# REDOUBLER.net
KiCad netlist of a schematic drawn in EAGLE
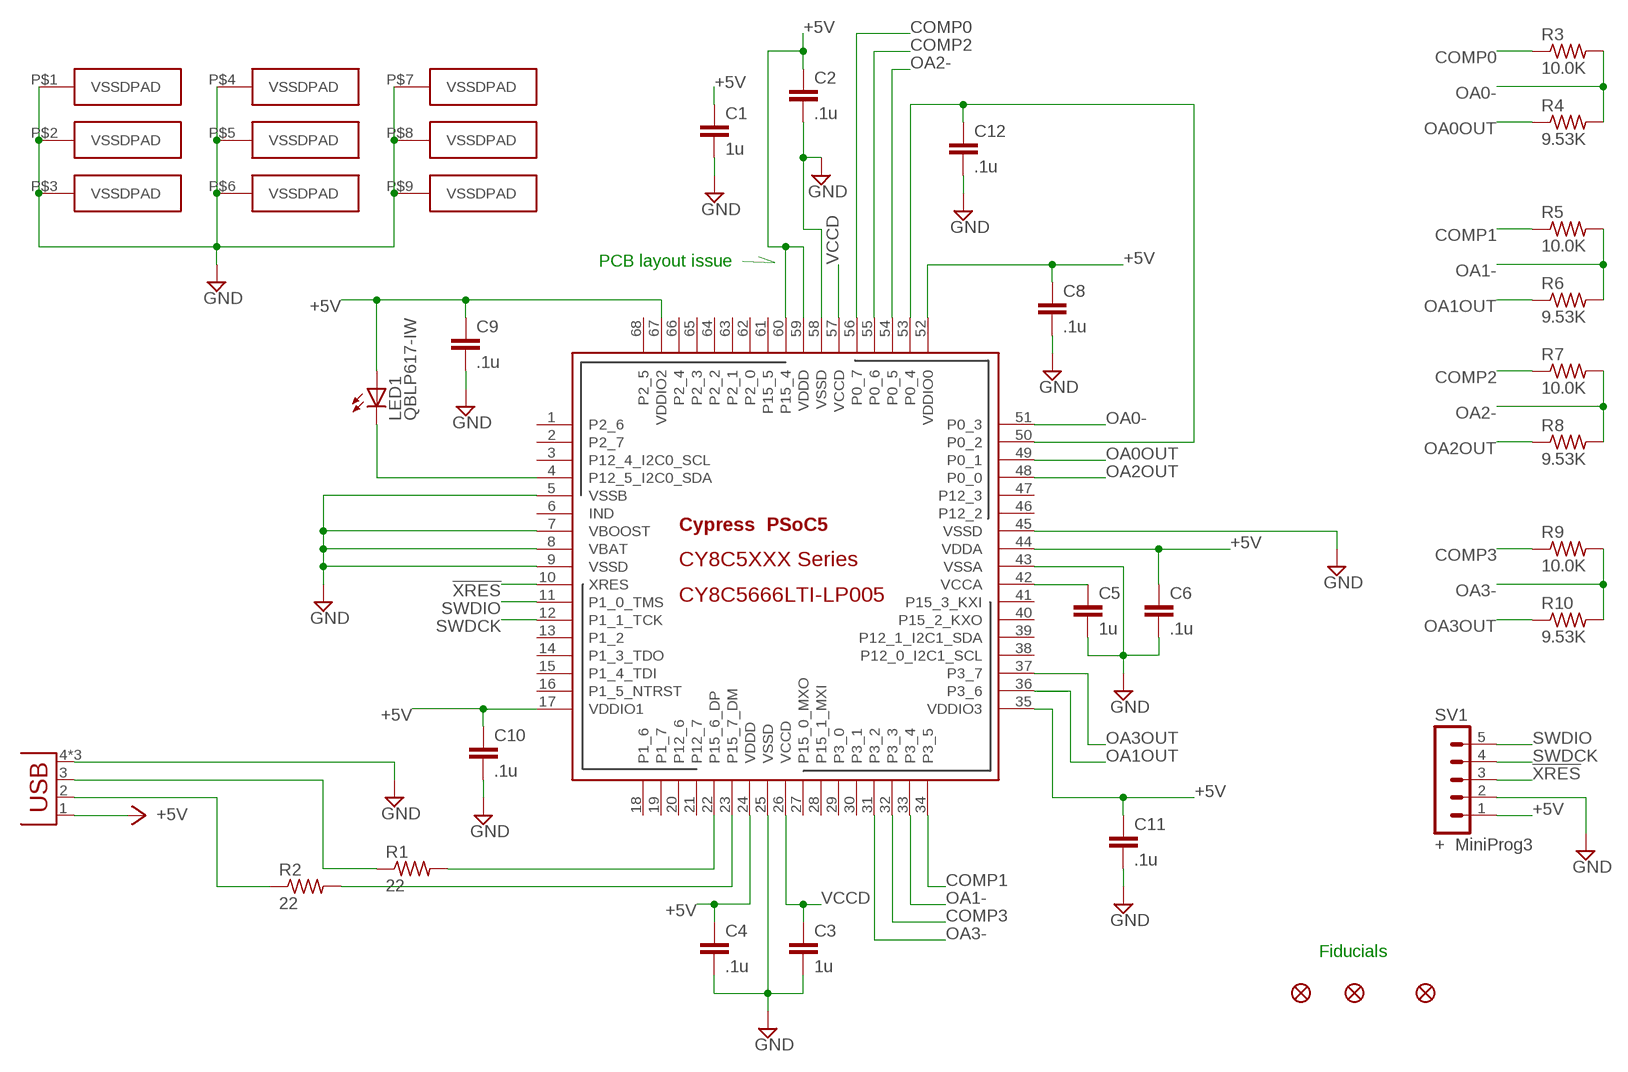
[diagram p0: schematic, sheet 1]

(export (version "E")
  (design (tool "Eeschema 10.0.6"))
  (components
    (comp (ref "C1")
      (value "1u")
      (footprint "eagle-import:C0402")
      (libsource (lib "eagle-import") (part "C-EUC0402"))
    )
    (comp (ref "C2")
      (value ".1u")
      (footprint "eagle-import:C0402")
      (libsource (lib "eagle-import") (part "C-EUC0402"))
    )
    (comp (ref "C3")
      (value "1u")
      (footprint "eagle-import:C0402")
      (libsource (lib "eagle-import") (part "C-EUC0402"))
    )
    (comp (ref "C4")
      (value ".1u")
      (footprint "eagle-import:C0402")
      (libsource (lib "eagle-import") (part "C-EUC0402"))
    )
    (comp (ref "C5")
      (value "1u")
      (footprint "eagle-import:C0402")
      (libsource (lib "eagle-import") (part "C-EUC0402"))
    )
    (comp (ref "C6")
      (value ".1u")
      (footprint "eagle-import:C0402")
      (libsource (lib "eagle-import") (part "C-EUC0402"))
    )
    (comp (ref "C8")
      (value ".1u")
      (footprint "eagle-import:C0402")
      (libsource (lib "eagle-import") (part "C-EUC0402"))
    )
    (comp (ref "C9")
      (value ".1u")
      (footprint "eagle-import:C0402")
      (libsource (lib "eagle-import") (part "C-EUC0402"))
    )
    (comp (ref "C10")
      (value ".1u")
      (footprint "eagle-import:C0402")
      (libsource (lib "eagle-import") (part "C-EUC0402"))
    )
    (comp (ref "C11")
      (value ".1u")
      (footprint "eagle-import:C0402")
      (libsource (lib "eagle-import") (part "C-EUC0402"))
    )
    (comp (ref "C12")
      (value ".1u")
      (footprint "eagle-import:C0402")
      (libsource (lib "eagle-import") (part "C-EUC0402"))
    )
    (comp (ref "FID1")
      (value "FIDUCIALUFIDUCIAL")
      (footprint "eagle-import:MICRO-FIDUCIAL")
      (libsource (lib "eagle-import") (part "FIDUCIALUFIDUCIAL"))
    )
    (comp (ref "FID2")
      (value "FIDUCIALUFIDUCIAL")
      (footprint "eagle-import:MICRO-FIDUCIAL")
      (libsource (lib "eagle-import") (part "FIDUCIALUFIDUCIAL"))
    )
    (comp (ref "FID3")
      (value "FIDUCIALUFIDUCIAL")
      (footprint "eagle-import:MICRO-FIDUCIAL")
      (libsource (lib "eagle-import") (part "FIDUCIALUFIDUCIAL"))
    )
    (comp (ref "LED1")
      (value "QBLP617-IW")
      (footprint "eagle-import:CHIP-LED0603")
      (libsource (lib "eagle-import") (part "LEDCHIP-LED0603"))
    )
    (comp (ref "R1")
      (value "22")
      (footprint "eagle-import:R0402")
      (libsource (lib "eagle-import") (part "R-US_R0402"))
    )
    (comp (ref "R2")
      (value "22")
      (footprint "eagle-import:R0402")
      (libsource (lib "eagle-import") (part "R-US_R0402"))
    )
    (comp (ref "R3")
      (value "10.0K")
      (footprint "eagle-import:R0402")
      (libsource (lib "eagle-import") (part "R-US_R0402"))
    )
    (comp (ref "R4")
      (value "9.53K")
      (footprint "eagle-import:R0402")
      (libsource (lib "eagle-import") (part "R-US_R0402"))
    )
    (comp (ref "R5")
      (value "10.0K")
      (footprint "eagle-import:R0402")
      (libsource (lib "eagle-import") (part "R-US_R0402"))
    )
    (comp (ref "R6")
      (value "9.53K")
      (footprint "eagle-import:R0402")
      (libsource (lib "eagle-import") (part "R-US_R0402"))
    )
    (comp (ref "R7")
      (value "10.0K")
      (footprint "eagle-import:R0402")
      (libsource (lib "eagle-import") (part "R-US_R0402"))
    )
    (comp (ref "R8")
      (value "9.53K")
      (footprint "eagle-import:R0402")
      (libsource (lib "eagle-import") (part "R-US_R0402"))
    )
    (comp (ref "R9")
      (value "10.0K")
      (footprint "eagle-import:R0402")
      (libsource (lib "eagle-import") (part "R-US_R0402"))
    )
    (comp (ref "R10")
      (value "9.53K")
      (footprint "eagle-import:R0402")
      (libsource (lib "eagle-import") (part "R-US_R0402"))
    )
    (comp (ref "SV1")
      (value "+ MiniProg3")
      (footprint "eagle-import:MA05-1")
      (libsource (lib "eagle-import") (part "MA05-1"))
    )
    (comp (ref "U$1")
      (value "CY8C5666LTI-LP005")
      (footprint "eagle-import:QFN68")
      (libsource (lib "eagle-import") (part "CY8C5XXX-68PIN"))
    )
    (comp (ref "X1")
      (value "USBSMT-MALE")
      (footprint "eagle-import:USB-A-SMT-MALE")
      (libsource (lib "eagle-import") (part "USBSMT-MALE"))
    )
  )
  (nets
    (net (code "1") (name "+5V") (class "Default")
      (node (ref "C1") (pin "1") (pinfunction "1_1") (pintype "passive"))
      (node (ref "C10") (pin "1") (pinfunction "1_1") (pintype "passive"))
      (node (ref "C11") (pin "1") (pinfunction "1_1") (pintype "passive"))
      (node (ref "C2") (pin "1") (pinfunction "1_1") (pintype "passive"))
      (node (ref "C4") (pin "1") (pinfunction "1_1") (pintype "passive"))
      (node (ref "C6") (pin "1") (pinfunction "1_1") (pintype "passive"))
      (node (ref "C8") (pin "1") (pinfunction "1_1") (pintype "passive"))
      (node (ref "C9") (pin "1") (pinfunction "1_1") (pintype "passive"))
      (node (ref "LED1") (pin "A") (pinfunction "A_A") (pintype "passive"))
      (node (ref "SV1") (pin "1") (pinfunction "1_1") (pintype "passive"))
      (node (ref "U$1") (pin "17") (pinfunction "VDDIO1_17") (pintype "passive"))
      (node (ref "U$1") (pin "24") (pinfunction "VDDD_24") (pintype "passive"))
      (node (ref "U$1") (pin "35") (pinfunction "VDDIO3_35") (pintype "passive"))
      (node (ref "U$1") (pin "44") (pinfunction "VDDA_44") (pintype "passive"))
      (node (ref "U$1") (pin "52") (pinfunction "VDDIO0_52") (pintype "passive"))
      (node (ref "U$1") (pin "59") (pinfunction "VDDD_59") (pintype "passive"))
      (node (ref "U$1") (pin "60") (pinfunction "P15_4_60") (pintype "passive"))
      (node (ref "U$1") (pin "67") (pinfunction "VDDIO2_67") (pintype "passive"))
      (node (ref "X1") (pin "1") (pinfunction "VCC_1") (pintype "bidirectional"))
    )
    (net (code "2") (name "/COMP0") (class "Default")
      (node (ref "R3") (pin "1") (pinfunction "1_1") (pintype "passive"))
      (node (ref "U$1") (pin "56") (pinfunction "P0_7_56") (pintype "passive"))
    )
    (net (code "3") (name "/COMP1") (class "Default")
      (node (ref "R5") (pin "1") (pinfunction "1_1") (pintype "passive"))
      (node (ref "U$1") (pin "34") (pinfunction "P3_5_34") (pintype "passive"))
    )
    (net (code "4") (name "/COMP2") (class "Default")
      (node (ref "R7") (pin "1") (pinfunction "1_1") (pintype "passive"))
      (node (ref "U$1") (pin "55") (pinfunction "P0_6_55") (pintype "passive"))
    )
    (net (code "5") (name "/COMP3") (class "Default")
      (node (ref "R9") (pin "1") (pinfunction "1_1") (pintype "passive"))
      (node (ref "U$1") (pin "32") (pinfunction "P3_3_32") (pintype "passive"))
    )
    (net (code "6") (name "/OA0-") (class "Default")
      (node (ref "R3") (pin "2") (pinfunction "2_2") (pintype "passive"))
      (node (ref "R4") (pin "2") (pinfunction "2_2") (pintype "passive"))
      (node (ref "U$1") (pin "51") (pinfunction "P0_3_51") (pintype "passive"))
    )
    (net (code "7") (name "/OA0OUT") (class "Default")
      (node (ref "R4") (pin "1") (pinfunction "1_1") (pintype "passive"))
      (node (ref "U$1") (pin "49") (pinfunction "P0_1_49") (pintype "passive"))
    )
    (net (code "8") (name "/OA1-") (class "Default")
      (node (ref "R5") (pin "2") (pinfunction "2_2") (pintype "passive"))
      (node (ref "R6") (pin "2") (pinfunction "2_2") (pintype "passive"))
      (node (ref "U$1") (pin "33") (pinfunction "P3_4_33") (pintype "passive"))
    )
    (net (code "9") (name "/OA1OUT") (class "Default")
      (node (ref "R6") (pin "1") (pinfunction "1_1") (pintype "passive"))
      (node (ref "U$1") (pin "36") (pinfunction "P3_6_36") (pintype "passive"))
    )
    (net (code "10") (name "/OA2-") (class "Default")
      (node (ref "R7") (pin "2") (pinfunction "2_2") (pintype "passive"))
      (node (ref "R8") (pin "2") (pinfunction "2_2") (pintype "passive"))
      (node (ref "U$1") (pin "54") (pinfunction "P0_5_54") (pintype "passive"))
    )
    (net (code "11") (name "/OA2OUT") (class "Default")
      (node (ref "R8") (pin "1") (pinfunction "1_1") (pintype "passive"))
      (node (ref "U$1") (pin "48") (pinfunction "P0_0_48") (pintype "passive"))
    )
    (net (code "12") (name "/OA3-") (class "Default")
      (node (ref "R10") (pin "2") (pinfunction "2_2") (pintype "passive"))
      (node (ref "R9") (pin "2") (pinfunction "2_2") (pintype "passive"))
      (node (ref "U$1") (pin "31") (pinfunction "P3_2_31") (pintype "passive"))
    )
    (net (code "13") (name "/OA3OUT") (class "Default")
      (node (ref "R10") (pin "1") (pinfunction "1_1") (pintype "passive"))
      (node (ref "U$1") (pin "37") (pinfunction "P3_7_37") (pintype "passive"))
    )
    (net (code "14") (name "/SWDCK") (class "Default")
      (node (ref "SV1") (pin "4") (pinfunction "4_4") (pintype "passive"))
      (node (ref "U$1") (pin "12") (pinfunction "P1_1_TCK_12") (pintype "passive"))
    )
    (net (code "15") (name "/SWDIO") (class "Default")
      (node (ref "SV1") (pin "5") (pinfunction "5_5") (pintype "passive"))
      (node (ref "U$1") (pin "11") (pinfunction "P1_0_TMS_11") (pintype "passive"))
    )
    (net (code "16") (name "/VCCD") (class "Default")
      (node (ref "C3") (pin "1") (pinfunction "1_1") (pintype "passive"))
      (node (ref "U$1") (pin "26") (pinfunction "VCCD_26") (pintype "passive"))
      (node (ref "U$1") (pin "57") (pinfunction "VCCD_57") (pintype "passive"))
    )
    (net (code "17") (name "/~{XRES}") (class "Default")
      (node (ref "SV1") (pin "3") (pinfunction "3_3") (pintype "passive"))
      (node (ref "U$1") (pin "10") (pinfunction "XRES_10") (pintype "passive"))
    )
    (net (code "18") (name "GND") (class "Default")
      (node (ref "C1") (pin "2") (pinfunction "2_2") (pintype "passive"))
      (node (ref "C10") (pin "2") (pinfunction "2_2") (pintype "passive"))
      (node (ref "C11") (pin "2") (pinfunction "2_2") (pintype "passive"))
      (node (ref "C12") (pin "2") (pinfunction "2_2") (pintype "passive"))
      (node (ref "C2") (pin "2") (pinfunction "2_2") (pintype "passive"))
      (node (ref "C3") (pin "2") (pinfunction "2_2") (pintype "passive"))
      (node (ref "C4") (pin "2") (pinfunction "2_2") (pintype "passive"))
      (node (ref "C5") (pin "2") (pinfunction "2_2") (pintype "passive"))
      (node (ref "C6") (pin "2") (pinfunction "2_2") (pintype "passive"))
      (node (ref "C8") (pin "2") (pinfunction "2_2") (pintype "passive"))
      (node (ref "C9") (pin "2") (pinfunction "2_2") (pintype "passive"))
      (node (ref "SV1") (pin "2") (pinfunction "2_2") (pintype "passive"))
      (node (ref "U$1") (pin "25") (pinfunction "VSSD_25") (pintype "passive"))
      (node (ref "U$1") (pin "43") (pinfunction "VSSA_43") (pintype "passive"))
      (node (ref "U$1") (pin "45") (pinfunction "VSSD_45") (pintype "passive"))
      (node (ref "U$1") (pin "5") (pinfunction "VSSB_5") (pintype "passive"))
      (node (ref "U$1") (pin "58") (pinfunction "VSSD_58") (pintype "passive"))
      (node (ref "U$1") (pin "7") (pinfunction "VBOOST_7") (pintype "passive"))
      (node (ref "U$1") (pin "8") (pinfunction "VBAT_8") (pintype "passive"))
      (node (ref "U$1") (pin "9") (pinfunction "VSSD_9") (pintype "passive"))
      (node (ref "U$1") (pin "P$1") (pinfunction "VSSDPAD_P$1") (pintype "power_in"))
      (node (ref "U$1") (pin "P$2") (pinfunction "VSSDPAD_P$2") (pintype "power_in"))
      (node (ref "U$1") (pin "P$3") (pinfunction "VSSDPAD_P$3") (pintype "power_in"))
      (node (ref "U$1") (pin "P$4") (pinfunction "VSSDPAD_P$4") (pintype "power_in"))
      (node (ref "U$1") (pin "P$5") (pinfunction "VSSDPAD_P$5") (pintype "power_in"))
      (node (ref "U$1") (pin "P$6") (pinfunction "VSSDPAD_P$6") (pintype "power_in"))
      (node (ref "U$1") (pin "P$7") (pinfunction "VSSDPAD_P$7") (pintype "power_in"))
      (node (ref "U$1") (pin "P$8") (pinfunction "VSSDPAD_P$8") (pintype "power_in"))
      (node (ref "U$1") (pin "P$9") (pinfunction "VSSDPAD_P$9") (pintype "power_in"))
      (node (ref "X1") (pin "4") (pinfunction "GND_4") (pintype "bidirectional"))
      (node (ref "X1") (pin "P$1") (pinfunction "GND_P$1") (pintype "bidirectional"))
      (node (ref "X1") (pin "P$3") (pinfunction "GND_P$3") (pintype "bidirectional"))
    )
    (net (code "19") (name "Net-(U$1A-P0_2)") (class "Default")
      (node (ref "C12") (pin "1") (pinfunction "1_1") (pintype "passive"))
      (node (ref "U$1") (pin "50") (pinfunction "P0_2_50") (pintype "passive"))
      (node (ref "U$1") (pin "53") (pinfunction "P0_4_53") (pintype "passive"))
    )
    (net (code "20") (name "Net-(U$1A-P12_5_I2C0_SDA)") (class "Default")
      (node (ref "LED1") (pin "C") (pinfunction "C_C") (pintype "passive"))
      (node (ref "U$1") (pin "4") (pinfunction "P12_5_I2C0_SDA_4") (pintype "passive"))
    )
    (net (code "21") (name "Net-(U$1A-P15_6_DP)") (class "Default")
      (node (ref "R1") (pin "2") (pinfunction "2_2") (pintype "passive"))
      (node (ref "U$1") (pin "22") (pinfunction "P15_6_DP_22") (pintype "passive"))
    )
    (net (code "22") (name "Net-(U$1A-P15_7_DM)") (class "Default")
      (node (ref "R2") (pin "2") (pinfunction "2_2") (pintype "passive"))
      (node (ref "U$1") (pin "23") (pinfunction "P15_7_DM_23") (pintype "passive"))
    )
    (net (code "23") (name "Net-(U$1A-VCCA)") (class "Default")
      (node (ref "C5") (pin "1") (pinfunction "1_1") (pintype "passive"))
      (node (ref "U$1") (pin "42") (pinfunction "VCCA_42") (pintype "passive"))
    )
    (net (code "24") (name "Net-(X1-D+)") (class "Default")
      (node (ref "R1") (pin "1") (pinfunction "1_1") (pintype "passive"))
      (node (ref "X1") (pin "3") (pinfunction "D+_3") (pintype "bidirectional"))
    )
    (net (code "25") (name "Net-(X1-D-)") (class "Default")
      (node (ref "R2") (pin "1") (pinfunction "1_1") (pintype "passive"))
      (node (ref "X1") (pin "2") (pinfunction "D-_2") (pintype "bidirectional"))
    )
    (net (code "26") (name "unconnected-(U$1A-IND-Pad6)") (class "Default")
      (node (ref "U$1") (pin "6") (pinfunction "IND_6") (pintype "passive"))
    )
    (net (code "27") (name "unconnected-(U$1A-P1_2-Pad13)") (class "Default")
      (node (ref "U$1") (pin "13") (pinfunction "P1_2_13") (pintype "passive"))
    )
    (net (code "28") (name "unconnected-(U$1A-P1_3_TDO-Pad14)") (class "Default")
      (node (ref "U$1") (pin "14") (pinfunction "P1_3_TDO_14") (pintype "passive"))
    )
    (net (code "29") (name "unconnected-(U$1A-P1_4_TDI-Pad15)") (class "Default")
      (node (ref "U$1") (pin "15") (pinfunction "P1_4_TDI_15") (pintype "passive"))
    )
    (net (code "30") (name "unconnected-(U$1A-P1_5_NTRST-Pad16)") (class "Default")
      (node (ref "U$1") (pin "16") (pinfunction "P1_5_NTRST_16") (pintype "passive"))
    )
    (net (code "31") (name "unconnected-(U$1A-P1_6-Pad18)") (class "Default")
      (node (ref "U$1") (pin "18") (pinfunction "P1_6_18") (pintype "passive"))
    )
    (net (code "32") (name "unconnected-(U$1A-P1_7-Pad19)") (class "Default")
      (node (ref "U$1") (pin "19") (pinfunction "P1_7_19") (pintype "passive"))
    )
    (net (code "33") (name "unconnected-(U$1A-P2_0-Pad62)") (class "Default")
      (node (ref "U$1") (pin "62") (pinfunction "P2_0_62") (pintype "passive"))
    )
    (net (code "34") (name "unconnected-(U$1A-P2_1-Pad63)") (class "Default")
      (node (ref "U$1") (pin "63") (pinfunction "P2_1_63") (pintype "passive"))
    )
    (net (code "35") (name "unconnected-(U$1A-P2_2-Pad64)") (class "Default")
      (node (ref "U$1") (pin "64") (pinfunction "P2_2_64") (pintype "passive"))
    )
    (net (code "36") (name "unconnected-(U$1A-P2_3-Pad65)") (class "Default")
      (node (ref "U$1") (pin "65") (pinfunction "P2_3_65") (pintype "passive"))
    )
    (net (code "37") (name "unconnected-(U$1A-P2_4-Pad66)") (class "Default")
      (node (ref "U$1") (pin "66") (pinfunction "P2_4_66") (pintype "passive"))
    )
    (net (code "38") (name "unconnected-(U$1A-P2_5-Pad68)") (class "Default")
      (node (ref "U$1") (pin "68") (pinfunction "P2_5_68") (pintype "passive"))
    )
    (net (code "39") (name "unconnected-(U$1A-P2_6-Pad1)") (class "Default")
      (node (ref "U$1") (pin "1") (pinfunction "P2_6_1") (pintype "passive"))
    )
    (net (code "40") (name "unconnected-(U$1A-P2_7-Pad2)") (class "Default")
      (node (ref "U$1") (pin "2") (pinfunction "P2_7_2") (pintype "passive"))
    )
    (net (code "41") (name "unconnected-(U$1A-P3_0-Pad29)") (class "Default")
      (node (ref "U$1") (pin "29") (pinfunction "P3_0_29") (pintype "passive"))
    )
    (net (code "42") (name "unconnected-(U$1A-P3_1-Pad30)") (class "Default")
      (node (ref "U$1") (pin "30") (pinfunction "P3_1_30") (pintype "passive"))
    )
    (net (code "43") (name "unconnected-(U$1A-P12_0_I2C1_SCL-Pad38)") (class "Default")
      (node (ref "U$1") (pin "38") (pinfunction "P12_0_I2C1_SCL_38") (pintype "passive"))
    )
    (net (code "44") (name "unconnected-(U$1A-P12_1_I2C1_SDA-Pad39)") (class "Default")
      (node (ref "U$1") (pin "39") (pinfunction "P12_1_I2C1_SDA_39") (pintype "passive"))
    )
    (net (code "45") (name "unconnected-(U$1A-P12_2-Pad46)") (class "Default")
      (node (ref "U$1") (pin "46") (pinfunction "P12_2_46") (pintype "passive"))
    )
    (net (code "46") (name "unconnected-(U$1A-P12_3-Pad47)") (class "Default")
      (node (ref "U$1") (pin "47") (pinfunction "P12_3_47") (pintype "passive"))
    )
    (net (code "47") (name "unconnected-(U$1A-P12_4_I2C0_SCL-Pad3)") (class "Default")
      (node (ref "U$1") (pin "3") (pinfunction "P12_4_I2C0_SCL_3") (pintype "passive"))
    )
    (net (code "48") (name "unconnected-(U$1A-P12_6-Pad20)") (class "Default")
      (node (ref "U$1") (pin "20") (pinfunction "P12_6_20") (pintype "passive"))
    )
    (net (code "49") (name "unconnected-(U$1A-P12_7-Pad21)") (class "Default")
      (node (ref "U$1") (pin "21") (pinfunction "P12_7_21") (pintype "passive"))
    )
    (net (code "50") (name "unconnected-(U$1A-P15_0_MXO-Pad27)") (class "Default")
      (node (ref "U$1") (pin "27") (pinfunction "P15_0_MXO_27") (pintype "passive"))
    )
    (net (code "51") (name "unconnected-(U$1A-P15_1_MXI-Pad28)") (class "Default")
      (node (ref "U$1") (pin "28") (pinfunction "P15_1_MXI_28") (pintype "passive"))
    )
    (net (code "52") (name "unconnected-(U$1A-P15_2_KXO-Pad40)") (class "Default")
      (node (ref "U$1") (pin "40") (pinfunction "P15_2_KXO_40") (pintype "passive"))
    )
    (net (code "53") (name "unconnected-(U$1A-P15_3_KXI-Pad41)") (class "Default")
      (node (ref "U$1") (pin "41") (pinfunction "P15_3_KXI_41") (pintype "passive"))
    )
    (net (code "54") (name "unconnected-(U$1A-P15_5-Pad61)") (class "Default")
      (node (ref "U$1") (pin "61") (pinfunction "P15_5_61") (pintype "passive"))
    )
  )
)
